# untitled.net
KiCad netlist of a schematic drawn in EAGLE
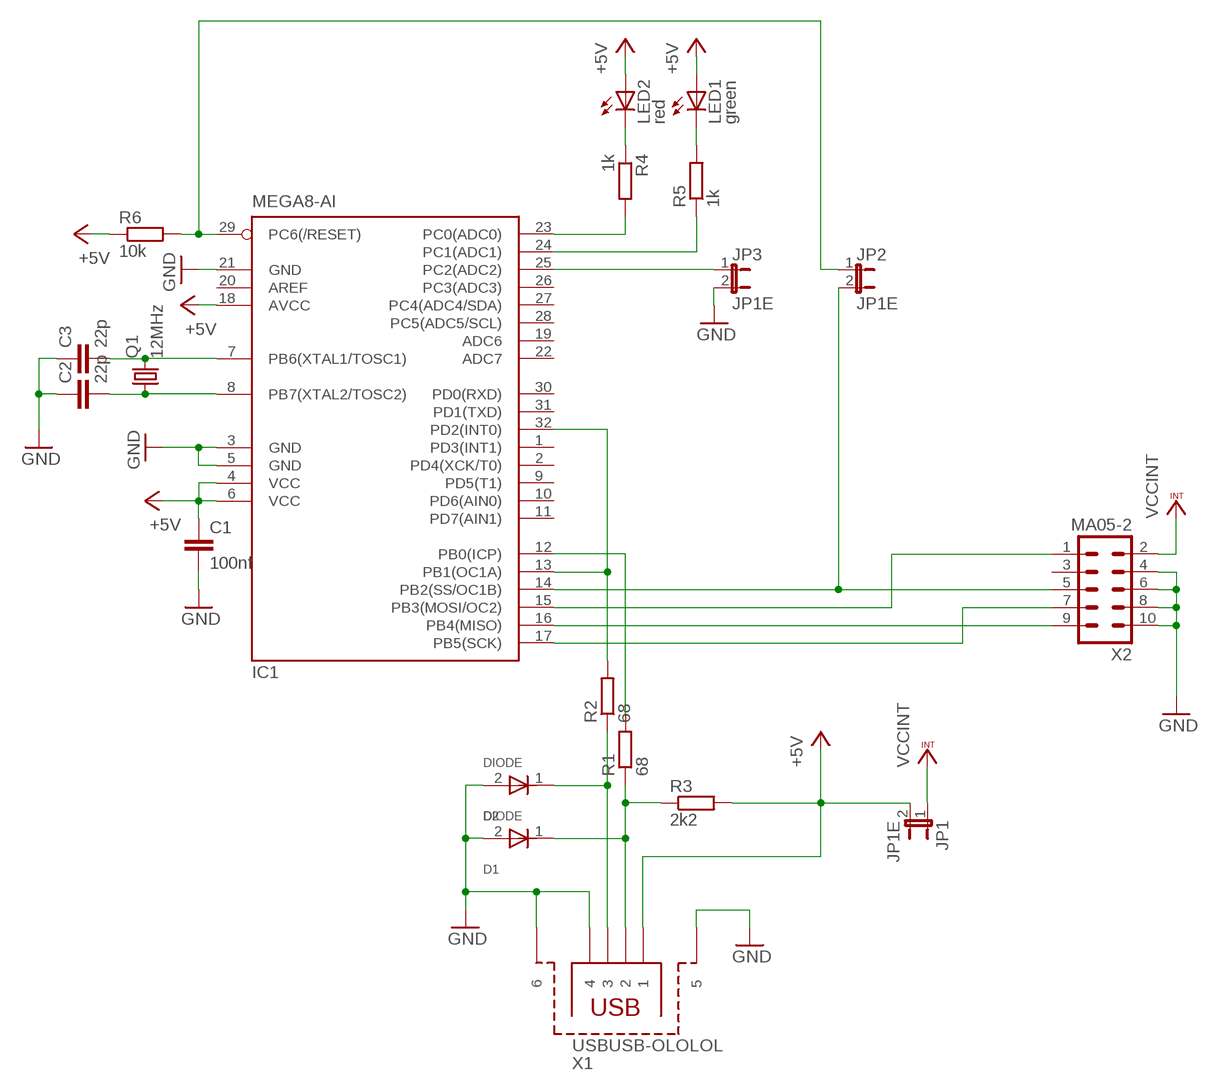
[diagram p0: schematic, sheet 1]

(export (version "E")
  (design (tool "Eeschema 10.0.6"))
  (components
    (comp (ref "C1")
      (value "100nf")
      (footprint "eagle-import:C0805")
      (libsource (lib "eagle-import") (part "C-EUC0805"))
    )
    (comp (ref "C2")
      (value "22p")
      (footprint "eagle-import:C0805")
      (libsource (lib "eagle-import") (part "C-EUC0805"))
    )
    (comp (ref "C3")
      (value "22p")
      (footprint "eagle-import:C0805")
      (libsource (lib "eagle-import") (part "C-EUC0805"))
    )
    (comp (ref "D1")
      (value "DIODE")
      (footprint "eagle-import:SOD80")
      (libsource (lib "eagle-import") (part "DIODE"))
    )
    (comp (ref "D2")
      (value "DIODE")
      (footprint "eagle-import:SOD80")
      (libsource (lib "eagle-import") (part "DIODE"))
    )
    (comp (ref "IC1")
      (value "MEGA8-AI")
      (footprint "eagle-import:TQFP32-08")
      (fields (field (name "MPN") "ATMEGA8-16AU"))
      (libsource (lib "eagle-import") (part "MEGA8-AI"))
    )
    (comp (ref "JP1")
      (value "JP1E")
      (footprint "eagle-import:JP0603")
      (libsource (lib "eagle-import") (part "JP1E"))
    )
    (comp (ref "JP2")
      (value "JP1E")
      (footprint "eagle-import:JP0603")
      (libsource (lib "eagle-import") (part "JP1E"))
    )
    (comp (ref "JP3")
      (value "JP1E")
      (footprint "eagle-import:JP0603")
      (libsource (lib "eagle-import") (part "JP1E"))
    )
    (comp (ref "LED1")
      (value "green")
      (footprint "eagle-import:CHIPLED_0805")
      (libsource (lib "eagle-import") (part "LEDCHIPLED_0805"))
    )
    (comp (ref "LED2")
      (value "red")
      (footprint "eagle-import:CHIPLED_0805")
      (libsource (lib "eagle-import") (part "LEDCHIPLED_0805"))
    )
    (comp (ref "Q1")
      (value "12MHz")
      (footprint "eagle-import:HC49_S")
      (libsource (lib "eagle-import") (part "CRYSTALHC49S"))
    )
    (comp (ref "R1")
      (value "68")
      (footprint "eagle-import:R0603")
      (libsource (lib "eagle-import") (part "R-EU_R0603"))
    )
    (comp (ref "R2")
      (value "68")
      (footprint "eagle-import:R0603")
      (libsource (lib "eagle-import") (part "R-EU_R0603"))
    )
    (comp (ref "R3")
      (value "2k2")
      (footprint "eagle-import:R0603")
      (libsource (lib "eagle-import") (part "R-EU_R0603"))
    )
    (comp (ref "R4")
      (value "1k")
      (footprint "eagle-import:R0603")
      (libsource (lib "eagle-import") (part "R-EU_R0603"))
    )
    (comp (ref "R5")
      (value "1k")
      (footprint "eagle-import:R0603")
      (libsource (lib "eagle-import") (part "R-EU_R0603"))
    )
    (comp (ref "R6")
      (value "10k")
      (footprint "eagle-import:R0603")
      (libsource (lib "eagle-import") (part "R-EU_R0603"))
    )
    (comp (ref "X1")
      (value "USBUSB-OLOLOL")
      (footprint "eagle-import:USB")
      (libsource (lib "eagle-import") (part "USBUSB-OLOLOL"))
    )
    (comp (ref "X2")
      (value "MA05-2")
      (footprint "eagle-import:MA05-2")
      (libsource (lib "eagle-import") (part "MA05-2"))
    )
  )
  (nets
    (net (code "1") (name "+5V") (class "Default")
      (node (ref "C1") (pin "1") (pinfunction "1_1") (pintype "passive"))
      (node (ref "IC1") (pin "18") (pinfunction "AVCC_18") (pintype "power_in"))
      (node (ref "IC1") (pin "4") (pinfunction "VCC_4") (pintype "power_in"))
      (node (ref "IC1") (pin "6") (pinfunction "VCC_6") (pintype "power_in"))
      (node (ref "JP1") (pin "2") (pinfunction "2_2") (pintype "passive"))
      (node (ref "LED1") (pin "A") (pinfunction "A_A") (pintype "passive"))
      (node (ref "LED2") (pin "A") (pinfunction "A_A") (pintype "passive"))
      (node (ref "R3") (pin "2") (pinfunction "2_2") (pintype "passive"))
      (node (ref "R6") (pin "1") (pinfunction "1_1") (pintype "passive"))
      (node (ref "X1") (pin "1") (pinfunction "1_1") (pintype "power_in"))
    )
    (net (code "2") (name "GND") (class "Default")
      (node (ref "C1") (pin "2") (pinfunction "2_2") (pintype "passive"))
      (node (ref "C2") (pin "1") (pinfunction "1_1") (pintype "passive"))
      (node (ref "C3") (pin "1") (pinfunction "1_1") (pintype "passive"))
      (node (ref "D1") (pin "2") (pinfunction "ANOD_2") (pintype "power_in"))
      (node (ref "D2") (pin "2") (pinfunction "ANOD_2") (pintype "power_in"))
      (node (ref "IC1") (pin "21") (pinfunction "GND_21") (pintype "power_in"))
      (node (ref "IC1") (pin "3") (pinfunction "GND_3") (pintype "power_in"))
      (node (ref "IC1") (pin "5") (pinfunction "GND_5") (pintype "power_in"))
      (node (ref "JP3") (pin "2") (pinfunction "2_2") (pintype "passive"))
      (node (ref "X1") (pin "4") (pinfunction "4_4") (pintype "power_in"))
      (node (ref "X1") (pin "5") (pinfunction "5_5") (pintype "power_in"))
      (node (ref "X1") (pin "6") (pinfunction "6_6") (pintype "power_in"))
      (node (ref "X2") (pin "10") (pinfunction "10_10") (pintype "passive"))
      (node (ref "X2") (pin "4") (pinfunction "4_4") (pintype "passive"))
      (node (ref "X2") (pin "6") (pinfunction "6_6") (pintype "passive"))
      (node (ref "X2") (pin "8") (pinfunction "8_8") (pintype "passive"))
    )
    (net (code "3") (name "Net-(D1-KATOD)") (class "Default")
      (node (ref "D1") (pin "1") (pinfunction "KATOD_1") (pintype "power_in"))
      (node (ref "R1") (pin "1") (pinfunction "1_1") (pintype "passive"))
      (node (ref "R3") (pin "1") (pinfunction "1_1") (pintype "passive"))
      (node (ref "X1") (pin "2") (pinfunction "2_2") (pintype "bidirectional"))
    )
    (net (code "4") (name "Net-(D2-KATOD)") (class "Default")
      (node (ref "D2") (pin "1") (pinfunction "KATOD_1") (pintype "power_in"))
      (node (ref "R2") (pin "1") (pinfunction "1_1") (pintype "passive"))
      (node (ref "X1") (pin "3") (pinfunction "3_3") (pintype "bidirectional"))
    )
    (net (code "5") (name "Net-(IC1-PB0(ICP))") (class "Default")
      (node (ref "IC1") (pin "12") (pinfunction "PB0(ICP)_12") (pintype "bidirectional"))
      (node (ref "R1") (pin "2") (pinfunction "2_2") (pintype "passive"))
    )
    (net (code "6") (name "Net-(IC1-PB1(OC1A))") (class "Default")
      (node (ref "IC1") (pin "13") (pinfunction "PB1(OC1A)_13") (pintype "bidirectional"))
      (node (ref "IC1") (pin "32") (pinfunction "PD2(INT0)_32") (pintype "bidirectional"))
      (node (ref "R2") (pin "2") (pinfunction "2_2") (pintype "passive"))
    )
    (net (code "7") (name "Net-(IC1-PB2(SS{slash}OC1B))") (class "Default")
      (node (ref "IC1") (pin "14") (pinfunction "PB2(SS/OC1B)_14") (pintype "bidirectional"))
      (node (ref "JP2") (pin "2") (pinfunction "2_2") (pintype "passive"))
      (node (ref "X2") (pin "5") (pinfunction "5_5") (pintype "passive"))
    )
    (net (code "8") (name "Net-(IC1-PB3(MOSI{slash}OC2))") (class "Default")
      (node (ref "IC1") (pin "15") (pinfunction "PB3(MOSI/OC2)_15") (pintype "bidirectional"))
      (node (ref "X2") (pin "1") (pinfunction "1_1") (pintype "passive"))
    )
    (net (code "9") (name "Net-(IC1-PB4(MISO))") (class "Default")
      (node (ref "IC1") (pin "16") (pinfunction "PB4(MISO)_16") (pintype "bidirectional"))
      (node (ref "X2") (pin "9") (pinfunction "9_9") (pintype "passive"))
    )
    (net (code "10") (name "Net-(IC1-PB5(SCK))") (class "Default")
      (node (ref "IC1") (pin "17") (pinfunction "PB5(SCK)_17") (pintype "bidirectional"))
      (node (ref "X2") (pin "7") (pinfunction "7_7") (pintype "passive"))
    )
    (net (code "11") (name "Net-(IC1-PB6(XTAL1{slash}TOSC1))") (class "Default")
      (node (ref "C3") (pin "2") (pinfunction "2_2") (pintype "passive"))
      (node (ref "IC1") (pin "7") (pinfunction "PB6(XTAL1/TOSC1)_7") (pintype "bidirectional"))
      (node (ref "Q1") (pin "2") (pinfunction "2_2") (pintype "passive"))
    )
    (net (code "12") (name "Net-(IC1-PB7(XTAL2{slash}TOSC2))") (class "Default")
      (node (ref "C2") (pin "2") (pinfunction "2_2") (pintype "passive"))
      (node (ref "IC1") (pin "8") (pinfunction "PB7(XTAL2/TOSC2)_8") (pintype "bidirectional"))
      (node (ref "Q1") (pin "1") (pinfunction "1_1") (pintype "passive"))
    )
    (net (code "13") (name "Net-(IC1-PC0(ADC0))") (class "Default")
      (node (ref "IC1") (pin "23") (pinfunction "PC0(ADC0)_23") (pintype "bidirectional"))
      (node (ref "R4") (pin "2") (pinfunction "2_2") (pintype "passive"))
    )
    (net (code "14") (name "Net-(IC1-PC1(ADC1))") (class "Default")
      (node (ref "IC1") (pin "24") (pinfunction "PC1(ADC1)_24") (pintype "bidirectional"))
      (node (ref "R5") (pin "1") (pinfunction "1_1") (pintype "passive"))
    )
    (net (code "15") (name "Net-(IC1-PC2(ADC2))") (class "Default")
      (node (ref "IC1") (pin "25") (pinfunction "PC2(ADC2)_25") (pintype "bidirectional"))
      (node (ref "JP3") (pin "1") (pinfunction "1_1") (pintype "passive"))
    )
    (net (code "16") (name "Net-(IC1-PC6({slash}RESET))") (class "Default")
      (node (ref "IC1") (pin "29") (pinfunction "PC6(/RESET)_29") (pintype "bidirectional"))
      (node (ref "JP2") (pin "1") (pinfunction "1_1") (pintype "passive"))
      (node (ref "R6") (pin "2") (pinfunction "2_2") (pintype "passive"))
    )
    (net (code "17") (name "Net-(LED1-PadC)") (class "Default")
      (node (ref "LED1") (pin "C") (pinfunction "C_C") (pintype "passive"))
      (node (ref "R5") (pin "2") (pinfunction "2_2") (pintype "passive"))
    )
    (net (code "18") (name "Net-(LED2-PadC)") (class "Default")
      (node (ref "LED2") (pin "C") (pinfunction "C_C") (pintype "passive"))
      (node (ref "R4") (pin "1") (pinfunction "1_1") (pintype "passive"))
    )
    (net (code "19") (name "VCCINT") (class "Default")
      (node (ref "JP1") (pin "1") (pinfunction "1_1") (pintype "passive"))
      (node (ref "X2") (pin "2") (pinfunction "2_2") (pintype "passive"))
    )
    (net (code "20") (name "unconnected-(IC1-ADC6-Pad19)") (class "Default")
      (node (ref "IC1") (pin "19") (pinfunction "ADC6_19") (pintype "bidirectional"))
    )
    (net (code "21") (name "unconnected-(IC1-ADC7-Pad22)") (class "Default")
      (node (ref "IC1") (pin "22") (pinfunction "ADC7_22") (pintype "bidirectional"))
    )
    (net (code "22") (name "unconnected-(IC1-AREF-Pad20)") (class "Default")
      (node (ref "IC1") (pin "20") (pinfunction "AREF_20") (pintype "passive"))
    )
    (net (code "23") (name "unconnected-(IC1-PC3(ADC3)-Pad26)") (class "Default")
      (node (ref "IC1") (pin "26") (pinfunction "PC3(ADC3)_26") (pintype "bidirectional"))
    )
    (net (code "24") (name "unconnected-(IC1-PC4(ADC4{slash}SDA)-Pad27)") (class "Default")
      (node (ref "IC1") (pin "27") (pinfunction "PC4(ADC4/SDA)_27") (pintype "bidirectional"))
    )
    (net (code "25") (name "unconnected-(IC1-PC5(ADC5{slash}SCL)-Pad28)") (class "Default")
      (node (ref "IC1") (pin "28") (pinfunction "PC5(ADC5/SCL)_28") (pintype "bidirectional"))
    )
    (net (code "26") (name "unconnected-(IC1-PD0(RXD)-Pad30)") (class "Default")
      (node (ref "IC1") (pin "30") (pinfunction "PD0(RXD)_30") (pintype "bidirectional"))
    )
    (net (code "27") (name "unconnected-(IC1-PD1(TXD)-Pad31)") (class "Default")
      (node (ref "IC1") (pin "31") (pinfunction "PD1(TXD)_31") (pintype "bidirectional"))
    )
    (net (code "28") (name "unconnected-(IC1-PD3(INT1)-Pad1)") (class "Default")
      (node (ref "IC1") (pin "1") (pinfunction "PD3(INT1)_1") (pintype "bidirectional"))
    )
    (net (code "29") (name "unconnected-(IC1-PD4(XCK{slash}T0)-Pad2)") (class "Default")
      (node (ref "IC1") (pin "2") (pinfunction "PD4(XCK/T0)_2") (pintype "bidirectional"))
    )
    (net (code "30") (name "unconnected-(IC1-PD5(T1)-Pad9)") (class "Default")
      (node (ref "IC1") (pin "9") (pinfunction "PD5(T1)_9") (pintype "bidirectional"))
    )
    (net (code "31") (name "unconnected-(IC1-PD6(AIN0)-Pad10)") (class "Default")
      (node (ref "IC1") (pin "10") (pinfunction "PD6(AIN0)_10") (pintype "bidirectional"))
    )
    (net (code "32") (name "unconnected-(IC1-PD7(AIN1)-Pad11)") (class "Default")
      (node (ref "IC1") (pin "11") (pinfunction "PD7(AIN1)_11") (pintype "bidirectional"))
    )
    (net (code "33") (name "unconnected-(X2-Pad3)") (class "Default")
      (node (ref "X2") (pin "3") (pinfunction "3_3") (pintype "passive"))
    )
  )
)
